# MAX1168_breakout.net
KiCad netlist of a schematic drawn in EAGLE
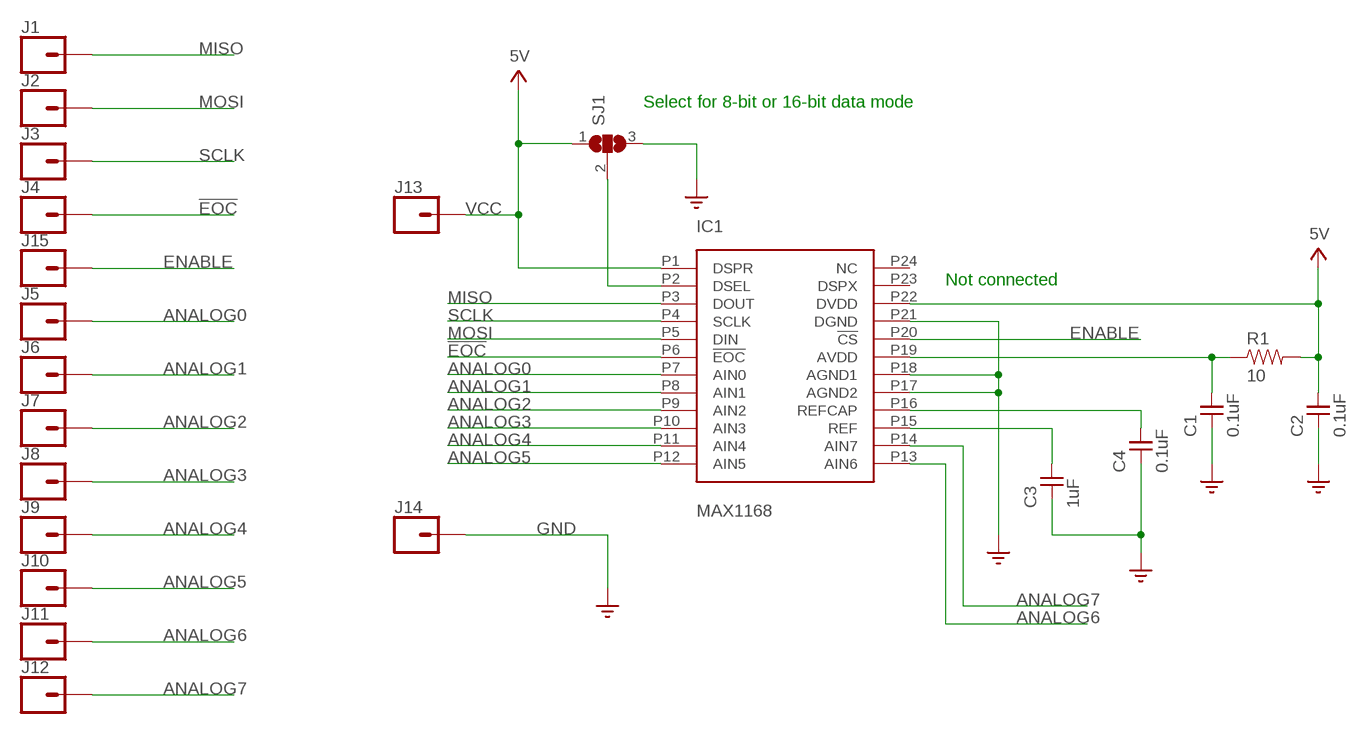
[diagram p0: schematic, sheet 1]

(export (version "E")
  (design (tool "Eeschema 10.0.6"))
  (components
    (comp (ref "C1")
      (value "0.1uF")
      (footprint "eagle-import:0805")
      (libsource (lib "eagle-import") (part "CAPACITOR0805"))
    )
    (comp (ref "C2")
      (value "0.1uF")
      (footprint "eagle-import:0805")
      (libsource (lib "eagle-import") (part "CAPACITOR0805"))
    )
    (comp (ref "C3")
      (value "1uF")
      (footprint "eagle-import:0805")
      (libsource (lib "eagle-import") (part "CAPACITOR0805"))
    )
    (comp (ref "C4")
      (value "0.1uF")
      (footprint "eagle-import:0805")
      (libsource (lib "eagle-import") (part "CAPACITOR0805"))
    )
    (comp (ref "IC1")
      (value "MAX1168")
      (footprint "eagle-import:QSOP-24")
      (libsource (lib "eagle-import") (part "MAX1168"))
    )
    (comp (ref "J1")
      (value "CONN_01PTH_NO_SILK_YES_STOP")
      (footprint "eagle-import:1X01_NO_SILK")
      (libsource (lib "eagle-import") (part "CONN_01PTH_NO_SILK_YES_STOP"))
    )
    (comp (ref "J2")
      (value "CONN_01PTH_NO_SILK_YES_STOP")
      (footprint "eagle-import:1X01_NO_SILK")
      (libsource (lib "eagle-import") (part "CONN_01PTH_NO_SILK_YES_STOP"))
    )
    (comp (ref "J3")
      (value "CONN_01PTH_NO_SILK_YES_STOP")
      (footprint "eagle-import:1X01_NO_SILK")
      (libsource (lib "eagle-import") (part "CONN_01PTH_NO_SILK_YES_STOP"))
    )
    (comp (ref "J4")
      (value "CONN_01PTH_NO_SILK_YES_STOP")
      (footprint "eagle-import:1X01_NO_SILK")
      (libsource (lib "eagle-import") (part "CONN_01PTH_NO_SILK_YES_STOP"))
    )
    (comp (ref "J5")
      (value "CONN_01PTH_NO_SILK_YES_STOP")
      (footprint "eagle-import:1X01_NO_SILK")
      (libsource (lib "eagle-import") (part "CONN_01PTH_NO_SILK_YES_STOP"))
    )
    (comp (ref "J6")
      (value "CONN_01PTH_NO_SILK_YES_STOP")
      (footprint "eagle-import:1X01_NO_SILK")
      (libsource (lib "eagle-import") (part "CONN_01PTH_NO_SILK_YES_STOP"))
    )
    (comp (ref "J7")
      (value "CONN_01PTH_NO_SILK_YES_STOP")
      (footprint "eagle-import:1X01_NO_SILK")
      (libsource (lib "eagle-import") (part "CONN_01PTH_NO_SILK_YES_STOP"))
    )
    (comp (ref "J8")
      (value "CONN_01PTH_NO_SILK_YES_STOP")
      (footprint "eagle-import:1X01_NO_SILK")
      (libsource (lib "eagle-import") (part "CONN_01PTH_NO_SILK_YES_STOP"))
    )
    (comp (ref "J9")
      (value "CONN_01PTH_NO_SILK_YES_STOP")
      (footprint "eagle-import:1X01_NO_SILK")
      (libsource (lib "eagle-import") (part "CONN_01PTH_NO_SILK_YES_STOP"))
    )
    (comp (ref "J10")
      (value "CONN_01PTH_NO_SILK_YES_STOP")
      (footprint "eagle-import:1X01_NO_SILK")
      (libsource (lib "eagle-import") (part "CONN_01PTH_NO_SILK_YES_STOP"))
    )
    (comp (ref "J11")
      (value "CONN_01PTH_NO_SILK_YES_STOP")
      (footprint "eagle-import:1X01_NO_SILK")
      (libsource (lib "eagle-import") (part "CONN_01PTH_NO_SILK_YES_STOP"))
    )
    (comp (ref "J12")
      (value "CONN_01PTH_NO_SILK_YES_STOP")
      (footprint "eagle-import:1X01_NO_SILK")
      (libsource (lib "eagle-import") (part "CONN_01PTH_NO_SILK_YES_STOP"))
    )
    (comp (ref "J13")
      (value "CONN_01PTH_NO_SILK_YES_STOP")
      (footprint "eagle-import:1X01_NO_SILK")
      (libsource (lib "eagle-import") (part "CONN_01PTH_NO_SILK_YES_STOP"))
    )
    (comp (ref "J14")
      (value "CONN_01PTH_NO_SILK_YES_STOP")
      (footprint "eagle-import:1X01_NO_SILK")
      (libsource (lib "eagle-import") (part "CONN_01PTH_NO_SILK_YES_STOP"))
    )
    (comp (ref "J15")
      (value "CONN_01PTH_NO_SILK_YES_STOP")
      (footprint "eagle-import:1X01_NO_SILK")
      (libsource (lib "eagle-import") (part "CONN_01PTH_NO_SILK_YES_STOP"))
    )
    (comp (ref "R1")
      (value "10")
      (footprint "eagle-import:0805")
      (libsource (lib "eagle-import") (part "RESISTOR0805SMD"))
    )
    (comp (ref "SJ1")
      (value "SJ2W")
      (footprint "eagle-import:SJ_2")
      (libsource (lib "eagle-import") (part "SJ2W"))
    )
  )
  (nets
    (net (code "1") (name "/ANALOG0") (class "Default")
      (node (ref "IC1") (pin "P7") (pinfunction "AIN0_P7") (pintype "bidirectional"))
      (node (ref "J5") (pin "1") (pinfunction "1_1") (pintype "passive"))
    )
    (net (code "2") (name "/ANALOG1") (class "Default")
      (node (ref "IC1") (pin "P8") (pinfunction "AIN1_P8") (pintype "bidirectional"))
      (node (ref "J6") (pin "1") (pinfunction "1_1") (pintype "passive"))
    )
    (net (code "3") (name "/ANALOG2") (class "Default")
      (node (ref "IC1") (pin "P9") (pinfunction "AIN2_P9") (pintype "bidirectional"))
      (node (ref "J7") (pin "1") (pinfunction "1_1") (pintype "passive"))
    )
    (net (code "4") (name "/ANALOG3") (class "Default")
      (node (ref "IC1") (pin "P10") (pinfunction "AIN3_P10") (pintype "bidirectional"))
      (node (ref "J8") (pin "1") (pinfunction "1_1") (pintype "passive"))
    )
    (net (code "5") (name "/ANALOG4") (class "Default")
      (node (ref "IC1") (pin "P11") (pinfunction "AIN4_P11") (pintype "bidirectional"))
      (node (ref "J9") (pin "1") (pinfunction "1_1") (pintype "passive"))
    )
    (net (code "6") (name "/ANALOG5") (class "Default")
      (node (ref "IC1") (pin "P12") (pinfunction "AIN5_P12") (pintype "bidirectional"))
      (node (ref "J10") (pin "1") (pinfunction "1_1") (pintype "passive"))
    )
    (net (code "7") (name "/ANALOG6") (class "Default")
      (node (ref "IC1") (pin "P13") (pinfunction "AIN6_P13") (pintype "bidirectional"))
      (node (ref "J11") (pin "1") (pinfunction "1_1") (pintype "passive"))
    )
    (net (code "8") (name "/ANALOG7") (class "Default")
      (node (ref "IC1") (pin "P14") (pinfunction "AIN7_P14") (pintype "bidirectional"))
      (node (ref "J12") (pin "1") (pinfunction "1_1") (pintype "passive"))
    )
    (net (code "9") (name "/ENABLE") (class "Default")
      (node (ref "IC1") (pin "P20") (pinfunction "~{CS}_P20") (pintype "bidirectional"))
      (node (ref "J15") (pin "1") (pinfunction "1_1") (pintype "passive"))
    )
    (net (code "10") (name "/MISO") (class "Default")
      (node (ref "IC1") (pin "P3") (pinfunction "DOUT_P3") (pintype "bidirectional"))
      (node (ref "J1") (pin "1") (pinfunction "1_1") (pintype "passive"))
    )
    (net (code "11") (name "/MOSI") (class "Default")
      (node (ref "IC1") (pin "P5") (pinfunction "DIN_P5") (pintype "bidirectional"))
      (node (ref "J2") (pin "1") (pinfunction "1_1") (pintype "passive"))
    )
    (net (code "12") (name "/SCLK") (class "Default")
      (node (ref "IC1") (pin "P4") (pinfunction "SCLK_P4") (pintype "bidirectional"))
      (node (ref "J3") (pin "1") (pinfunction "1_1") (pintype "passive"))
    )
    (net (code "13") (name "/~{EOC}") (class "Default")
      (node (ref "IC1") (pin "P6") (pinfunction "~{EOC}_P6") (pintype "bidirectional"))
      (node (ref "J4") (pin "1") (pinfunction "1_1") (pintype "passive"))
    )
    (net (code "14") (name "5V") (class "Default")
      (node (ref "C2") (pin "2") (pinfunction "2_2") (pintype "passive"))
      (node (ref "IC1") (pin "P1") (pinfunction "DSPR_P1") (pintype "bidirectional"))
      (node (ref "IC1") (pin "P22") (pinfunction "DVDD_P22") (pintype "bidirectional"))
      (node (ref "J13") (pin "1") (pinfunction "1_1") (pintype "passive"))
      (node (ref "R1") (pin "2") (pinfunction "2_2") (pintype "passive"))
      (node (ref "SJ1") (pin "1") (pinfunction "1_1") (pintype "passive"))
    )
    (net (code "15") (name "DGND") (class "Default")
      (node (ref "C1") (pin "1") (pinfunction "1_1") (pintype "passive"))
      (node (ref "C2") (pin "1") (pinfunction "1_1") (pintype "passive"))
      (node (ref "C3") (pin "1") (pinfunction "1_1") (pintype "passive"))
      (node (ref "C4") (pin "1") (pinfunction "1_1") (pintype "passive"))
      (node (ref "IC1") (pin "P17") (pinfunction "AGND2_P17") (pintype "bidirectional"))
      (node (ref "IC1") (pin "P18") (pinfunction "AGND1_P18") (pintype "bidirectional"))
      (node (ref "IC1") (pin "P21") (pinfunction "DGND_P21") (pintype "bidirectional"))
      (node (ref "J14") (pin "1") (pinfunction "1_1") (pintype "passive"))
      (node (ref "SJ1") (pin "3") (pinfunction "3_3") (pintype "passive"))
    )
    (net (code "16") (name "Net-(IC1-AVDD)") (class "Default")
      (node (ref "C1") (pin "2") (pinfunction "2_2") (pintype "passive"))
      (node (ref "IC1") (pin "P19") (pinfunction "AVDD_P19") (pintype "bidirectional"))
      (node (ref "R1") (pin "1") (pinfunction "1_1") (pintype "passive"))
    )
    (net (code "17") (name "Net-(IC1-DSEL)") (class "Default")
      (node (ref "IC1") (pin "P2") (pinfunction "DSEL_P2") (pintype "bidirectional"))
      (node (ref "SJ1") (pin "2") (pinfunction "2_2") (pintype "passive"))
    )
    (net (code "18") (name "Net-(IC1-REF)") (class "Default")
      (node (ref "C3") (pin "2") (pinfunction "2_2") (pintype "passive"))
      (node (ref "IC1") (pin "P15") (pinfunction "REF_P15") (pintype "bidirectional"))
    )
    (net (code "19") (name "Net-(IC1-REFCAP)") (class "Default")
      (node (ref "C4") (pin "2") (pinfunction "2_2") (pintype "passive"))
      (node (ref "IC1") (pin "P16") (pinfunction "REFCAP_P16") (pintype "bidirectional"))
    )
    (net (code "20") (name "unconnected-(IC1-DSPX-PadP23)") (class "Default")
      (node (ref "IC1") (pin "P23") (pinfunction "DSPX_P23") (pintype "bidirectional"))
    )
    (net (code "21") (name "unconnected-(IC1-NC-PadP24)") (class "Default")
      (node (ref "IC1") (pin "P24") (pinfunction "NC_P24") (pintype "bidirectional"))
    )
  )
)
